# Pag4_Processador.net
KiCad netlist of a schematic drawn in Altium Designer
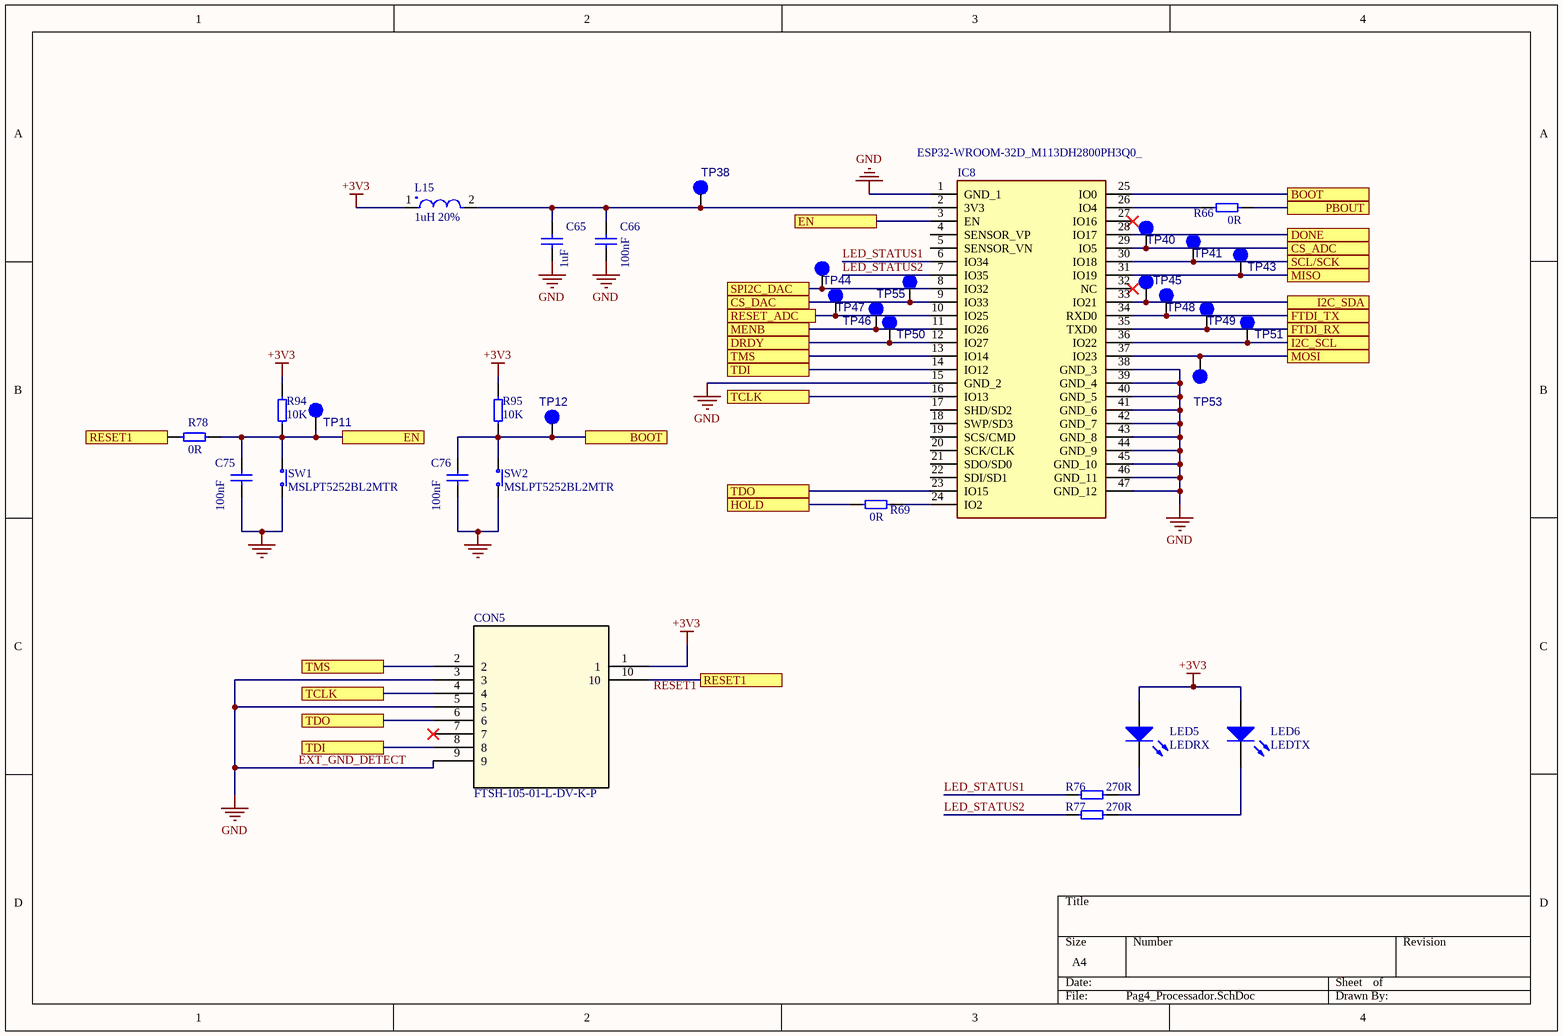
[diagram p0: Pag4_Processador.SchDoc]

(export (version "E")
  (design (tool "Eeschema 10.0.6"))
  (components
    (comp (ref "C65")
      (value "1uF")
      (footprint "0603")
      (description "Multilayer Ceramic Capacitors MLCC - SMD/SMT 1uF 25V 0603 10%")
      (fields
        (field (name "MANUFACTURER") "Samsung Electro-Mechanics")
        (field (name "MPN") "CL10A105KA8NNNC")
      )
      (libsource (lib "potenciostato") (part "CAP_1uF"))
    )
    (comp (ref "C66")
      (value "100nF")
      (footprint "0603")
      (description "Multilayer Ceramic Capacitors MLCC - SMD/SMT 100nF 16V 0603 10%")
      (fields (field (name "MPN") "C0603C104K4RACTU") (field (name "MANUFACTURER") "Kemet"))
      (libsource (lib "potenciostato") (part "Cap_1"))
    )
    (comp (ref "C75")
      (value "100nF")
      (footprint "0603")
      (description "Multilayer Ceramic Capacitors MLCC - SMD/SMT 100nF 16V 0603 10%")
      (fields (field (name "MPN") "C0603C104K4RACTU") (field (name "MANUFACTURER") "Kemet"))
      (libsource (lib "potenciostato") (part "Cap_1"))
    )
    (comp (ref "C76")
      (value "100nF")
      (footprint "0603")
      (description "Multilayer Ceramic Capacitors MLCC - SMD/SMT 100nF 16V 0603 10%")
      (fields (field (name "MPN") "C0603C104K4RACTU") (field (name "MANUFACTURER") "Kemet"))
      (libsource (lib "potenciostato") (part "Cap_1"))
    )
    (comp (ref "CON5")
      (value "FTSH-105-01-L-DV-K-P")
      (footprint "SAMTEC_FTSH-105-XX-X-DV")
      (description "No Description Available")
      (fields (field (name "MANUFACTURER") "Samtec") (field (name "MPN") "FTSH-105-01-L-DV-K-P-TR"))
      (libsource (lib "FTSH-105-01-L-DV-K-P") (part "FTSH-105-01-L-DV-K-P"))
    )
    (comp (ref "IC8")
      (value "ESP32-WROOM-32D_M113DH2800PH3Q0_")
      (footprint "SamacSys:ESP32WROOM32DM113DH2800PH3Q0")
      (description "Integrated Circuit")
      (fields
        (field (name "MANUFACTURER") "Espressif Systems")
        (field (name "MPN") "ESP32-WROOM-32D(M113DH2800PH3Q0)")
      )
      (libsource (lib "*") (part "ESP32-WROOM-32D_M113DH2800PH3Q0_"))
    )
    (comp (ref "L15")
      (value "1uH 20%")
      (footprint "SRP4020-1R5M")
      (description "Power Inductors - SMD 1uH 20% SMD 4012 AEC-Q200")
      (fields (field (name "MANUFACTURER") "Bourns") (field (name "MPN") "SRP4012TA-1R0M"))
      (libsource (lib "potenciostato") (part "IC_1uH"))
    )
    (comp (ref "LED5")
      (value "LEDRX")
      (footprint "0603 - LED")
      (description "Standard LEDs - SMD 0603 SMT CHIP LED 572nm")
      (fields (field (name "MANUFACTURER") "ROHM Semiconductor") (field (name "MPN") "SML-D13M8WT86"))
      (libsource (lib "LIBSCH_PULLUP") (part "LED"))
    )
    (comp (ref "LED6")
      (value "LEDTX")
      (footprint "0603 - LED")
      (description "Standard LEDs - SMD 0603 SMT CHIP LED 572nm")
      (fields (field (name "MANUFACTURER") "ROHM Semiconductor") (field (name "MPN") "SML-D13M8WT86"))
      (libsource (lib "LIBSCH_PULLUP") (part "LED"))
    )
    (comp (ref "R66")
      (value "0R")
      (footprint "0603")
      (description "Thick Film Resistors - SMD 0 Ohms 100 mW 0603 5%")
      (fields (field (name "MPN") "RC0603JR-070RL") (field (name "MANUFACTURER") "Yageo"))
      (libsource (lib "potenciostato") (part "Pullup_Res_0_0603_RES"))
    )
    (comp (ref "R69")
      (value "0R")
      (footprint "0603")
      (description "Thick Film Resistors - SMD 0 Ohms 100 mW 0603 5%")
      (fields (field (name "MPN") "RC0603JR-070RL") (field (name "MANUFACTURER") "Yageo"))
      (libsource (lib "potenciostato") (part "Pullup_Res_0_0603_RES"))
    )
    (comp (ref "R76")
      (value "270R")
      (footprint "0603_2")
      (description "Thick Film Resistors - SMD 270 Ohms 0603 100mW 1%")
      (fields (field (name "MANUFACTURER") "Yageo") (field (name "MPN") "RC0603FR-07270RL"))
      (libsource (lib "LIBSCH_PULLUP") (part "Res"))
    )
    (comp (ref "R77")
      (value "270R")
      (footprint "0603_2")
      (description "Thick Film Resistors - SMD 270 Ohms 0603 100mW 1%")
      (fields (field (name "MANUFACTURER") "Yageo") (field (name "MPN") "RC0603FR-07270RL"))
      (libsource (lib "LIBSCH_PULLUP") (part "Res"))
    )
    (comp (ref "R78")
      (value "0R")
      (footprint "0603")
      (description "Thick Film Resistors - SMD 0 Ohms 100 mW 0603 5%")
      (fields (field (name "MPN") "RC0603JR-070RL") (field (name "MANUFACTURER") "Yageo"))
      (libsource (lib "potenciostato") (part "Pullup_Res_0_0603_RES"))
    )
    (comp (ref "R94")
      (value "10K")
      (footprint "0603")
      (description "Thick Film Resistors - SMD 10 kOhms 100-200 mW 0603 1%")
      (fields (field (name "MPN") "RC0603FR-1310KL") (field (name "MANUFACTURER") "Yageo"))
      (libsource (lib "potenciostato") (part "Pullup_Res_100K_0603_RES"))
    )
    (comp (ref "R95")
      (value "10K")
      (footprint "0603")
      (description "Thick Film Resistors - SMD 10 kOhms 100-200 mW 0603 1%")
      (fields (field (name "MPN") "RC0603FR-1310KL") (field (name "MANUFACTURER") "Yageo"))
      (libsource (lib "potenciostato") (part "Pullup_Res_100K_0603_RES"))
    )
    (comp (ref "SW1")
      (value "MSLPT5252BL2MTR")
      (footprint "MSLPT5252BG1MTR_pullup")
      (description "Tactile Switch, SPNO, SMD, 160gf, 6.2x6.3x2.5mm")
      (fields (field (name "MANUFACTURER") "TE Connectivity / Alcoswitch"))
      (libsource (lib "Nordic Discrete DB") (part "SW-PB"))
    )
    (comp (ref "SW2")
      (value "MSLPT5252BL2MTR")
      (footprint "MSLPT5252BG1MTR_pullup")
      (description "Tactile Switch, SPNO, SMD, 160gf, 6.2x6.3x2.5mm")
      (fields (field (name "MANUFACTURER") "TE Connectivity / Alcoswitch"))
      (libsource (lib "Nordic Discrete DB") (part "SW-PB"))
    )
    (comp (ref "TP11")
      (value "Test Point")
      (footprint "TEST")
      (fields (field (name "MPN") "Test_Point") (field (name "MANUFACTURER") "DNA"))
      (libsource (lib "potenciostato") (part "TESTPOINT"))
    )
    (comp (ref "TP12")
      (value "Test Point")
      (footprint "TEST")
      (fields (field (name "MPN") "Test_Point") (field (name "MANUFACTURER") "DNA"))
      (libsource (lib "potenciostato") (part "TESTPOINT"))
    )
    (comp (ref "TP38")
      (value "Test Point")
      (footprint "TEST")
      (fields (field (name "MPN") "Test_Point") (field (name "MANUFACTURER") "DNA"))
      (libsource (lib "potenciostato") (part "TESTPOINT"))
    )
    (comp (ref "TP40")
      (value "Test Point")
      (footprint "TEST")
      (fields (field (name "MPN") "Test_Point") (field (name "MANUFACTURER") "DNA"))
      (libsource (lib "potenciostato") (part "TESTPOINT"))
    )
    (comp (ref "TP41")
      (value "Test Point")
      (footprint "TEST")
      (fields (field (name "MPN") "Test_Point") (field (name "MANUFACTURER") "DNA"))
      (libsource (lib "potenciostato") (part "TESTPOINT"))
    )
    (comp (ref "TP43")
      (value "Test Point")
      (footprint "TEST")
      (fields (field (name "MPN") "Test_Point") (field (name "MANUFACTURER") "DNA"))
      (libsource (lib "potenciostato") (part "TESTPOINT"))
    )
    (comp (ref "TP44")
      (value "Test Point")
      (footprint "TEST")
      (fields (field (name "MPN") "Test_Point") (field (name "MANUFACTURER") "DNA"))
      (libsource (lib "potenciostato") (part "TESTPOINT"))
    )
    (comp (ref "TP45")
      (value "Test Point")
      (footprint "TEST")
      (fields (field (name "MPN") "Test_Point") (field (name "MANUFACTURER") "DNA"))
      (libsource (lib "potenciostato") (part "TESTPOINT"))
    )
    (comp (ref "TP46")
      (value "Test Point")
      (footprint "TEST")
      (fields (field (name "MPN") "Test_Point") (field (name "MANUFACTURER") "DNA"))
      (libsource (lib "potenciostato") (part "TESTPOINT"))
    )
    (comp (ref "TP47")
      (value "Test Point")
      (footprint "TEST")
      (fields (field (name "MPN") "Test_Point") (field (name "MANUFACTURER") "DNA"))
      (libsource (lib "potenciostato") (part "TESTPOINT"))
    )
    (comp (ref "TP48")
      (value "Test Point")
      (footprint "TEST")
      (fields (field (name "MPN") "Test_Point") (field (name "MANUFACTURER") "DNA"))
      (libsource (lib "potenciostato") (part "TESTPOINT"))
    )
    (comp (ref "TP49")
      (value "Test Point")
      (footprint "TEST")
      (fields (field (name "MPN") "Test_Point") (field (name "MANUFACTURER") "DNA"))
      (libsource (lib "potenciostato") (part "TESTPOINT"))
    )
    (comp (ref "TP50")
      (value "Test Point")
      (footprint "TEST")
      (fields (field (name "MPN") "Test_Point") (field (name "MANUFACTURER") "DNA"))
      (libsource (lib "potenciostato") (part "TESTPOINT"))
    )
    (comp (ref "TP51")
      (value "Test Point")
      (footprint "TEST")
      (fields (field (name "MPN") "Test_Point") (field (name "MANUFACTURER") "DNA"))
      (libsource (lib "potenciostato") (part "TESTPOINT"))
    )
    (comp (ref "TP53")
      (value "Test Point")
      (footprint "TEST")
      (fields (field (name "MPN") "Test_Point") (field (name "MANUFACTURER") "DNA"))
      (libsource (lib "potenciostato") (part "TESTPOINT"))
    )
    (comp (ref "TP55")
      (value "Test Point")
      (footprint "TEST")
      (fields (field (name "MPN") "Test_Point") (field (name "MANUFACTURER") "DNA"))
      (libsource (lib "potenciostato") (part "TESTPOINT"))
    )
  )
  (nets
    (net (code "1") (name "+3V3") (class "Default")
      (node (ref "CON5") (pin "1") (pinfunction "1_1") (pintype "passive"))
      (node (ref "L15") (pin "1") (pinfunction "1_1") (pintype "passive"))
      (node (ref "LED5") (pin "1") (pinfunction "A_1") (pintype "passive"))
      (node (ref "LED6") (pin "1") (pinfunction "A_1") (pintype "passive"))
      (node (ref "R94") (pin "2") (pinfunction "2_2") (pintype "passive"))
      (node (ref "R95") (pin "2") (pinfunction "2_2") (pintype "passive"))
    )
    (net (code "2") (name "/BOOT") (class "Default")
      (node (ref "C76") (pin "2") (pinfunction "2_2") (pintype "passive"))
      (node (ref "IC8") (pin "25") (pinfunction "IO0_25") (pintype "passive"))
      (node (ref "R95") (pin "1") (pinfunction "1_1") (pintype "passive"))
      (node (ref "SW2") (pin "2") (pinfunction "COM_2") (pintype "passive"))
      (node (ref "TP12") (pin "1") (pinfunction "TP_1") (pintype "passive"))
    )
    (net (code "3") (name "/CS_ADC") (class "Default")
      (node (ref "IC8") (pin "29") (pinfunction "IO5_29") (pintype "passive"))
      (node (ref "TP40") (pin "1") (pinfunction "TP_1") (pintype "passive"))
    )
    (net (code "4") (name "/CS_DAC") (class "Default")
      (node (ref "IC8") (pin "9") (pinfunction "IO33_9") (pintype "passive"))
      (node (ref "TP55") (pin "1") (pinfunction "TP_1") (pintype "passive"))
    )
    (net (code "5") (name "/DONE") (class "Default")
      (node (ref "IC8") (pin "28") (pinfunction "IO17_28") (pintype "passive"))
    )
    (net (code "6") (name "/DRDY") (class "Default")
      (node (ref "IC8") (pin "12") (pinfunction "IO27_12") (pintype "passive"))
      (node (ref "TP50") (pin "1") (pinfunction "TP_1") (pintype "passive"))
    )
    (net (code "7") (name "/EN") (class "Default")
      (node (ref "C75") (pin "2") (pinfunction "2_2") (pintype "passive"))
      (node (ref "IC8") (pin "3") (pinfunction "EN_3") (pintype "passive"))
      (node (ref "R78") (pin "1") (pinfunction "1_1") (pintype "passive"))
      (node (ref "R94") (pin "1") (pinfunction "1_1") (pintype "passive"))
      (node (ref "SW1") (pin "2") (pinfunction "COM_2") (pintype "passive"))
      (node (ref "TP11") (pin "1") (pinfunction "TP_1") (pintype "passive"))
    )
    (net (code "8") (name "/FTDI_RX") (class "Default")
      (node (ref "IC8") (pin "35") (pinfunction "TXD0_35") (pintype "passive"))
      (node (ref "TP49") (pin "1") (pinfunction "TP_1") (pintype "passive"))
    )
    (net (code "9") (name "/FTDI_TX") (class "Default")
      (node (ref "IC8") (pin "34") (pinfunction "RXD0_34") (pintype "passive"))
      (node (ref "TP48") (pin "1") (pinfunction "TP_1") (pintype "passive"))
    )
    (net (code "10") (name "/HOLD") (class "Default")
      (node (ref "R69") (pin "2") (pinfunction "2_2") (pintype "passive"))
    )
    (net (code "11") (name "/I2C_SCL") (class "Default")
      (node (ref "IC8") (pin "36") (pinfunction "IO22_36") (pintype "passive"))
      (node (ref "TP51") (pin "1") (pinfunction "TP_1") (pintype "passive"))
    )
    (net (code "12") (name "/I2C_SDA") (class "Default")
      (node (ref "IC8") (pin "33") (pinfunction "IO21_33") (pintype "passive"))
      (node (ref "TP45") (pin "1") (pinfunction "TP_1") (pintype "passive"))
    )
    (net (code "13") (name "/LED_STATUS1") (class "Default")
      (node (ref "IC8") (pin "6") (pinfunction "IO34_6") (pintype "passive"))
      (node (ref "R76") (pin "1") (pinfunction "1_1") (pintype "passive"))
    )
    (net (code "14") (name "/LED_STATUS2") (class "Default")
      (node (ref "IC8") (pin "7") (pinfunction "IO35_7") (pintype "passive"))
      (node (ref "R77") (pin "1") (pinfunction "1_1") (pintype "passive"))
    )
    (net (code "15") (name "/MENB") (class "Default")
      (node (ref "IC8") (pin "11") (pinfunction "IO26_11") (pintype "passive"))
      (node (ref "TP46") (pin "1") (pinfunction "TP_1") (pintype "passive"))
    )
    (net (code "16") (name "/MISO") (class "Default")
      (node (ref "IC8") (pin "31") (pinfunction "IO19_31") (pintype "passive"))
      (node (ref "TP43") (pin "1") (pinfunction "TP_1") (pintype "passive"))
    )
    (net (code "17") (name "/MOSI") (class "Default")
      (node (ref "IC8") (pin "37") (pinfunction "IO23_37") (pintype "passive"))
      (node (ref "TP53") (pin "1") (pinfunction "TP_1") (pintype "passive"))
    )
    (net (code "18") (name "/PBOUT") (class "Default")
      (node (ref "R66") (pin "1") (pinfunction "1_1") (pintype "passive"))
    )
    (net (code "19") (name "/RESET1") (class "Default")
      (node (ref "CON5") (pin "10") (pinfunction "10_10") (pintype "passive"))
      (node (ref "R78") (pin "2") (pinfunction "2_2") (pintype "passive"))
    )
    (net (code "20") (name "/RESET_ADC") (class "Default")
      (node (ref "IC8") (pin "10") (pinfunction "IO25_10") (pintype "passive"))
      (node (ref "TP47") (pin "1") (pinfunction "TP_1") (pintype "passive"))
    )
    (net (code "21") (name "/SCL{slash}SCK") (class "Default")
      (node (ref "IC8") (pin "30") (pinfunction "IO18_30") (pintype "passive"))
      (node (ref "TP41") (pin "1") (pinfunction "TP_1") (pintype "passive"))
    )
    (net (code "22") (name "/SPI2C_DAC") (class "Default")
      (node (ref "IC8") (pin "8") (pinfunction "IO32_8") (pintype "passive"))
      (node (ref "TP44") (pin "1") (pinfunction "TP_1") (pintype "passive"))
    )
    (net (code "23") (name "/TCLK") (class "Default")
      (node (ref "CON5") (pin "4") (pinfunction "4_4") (pintype "passive"))
      (node (ref "IC8") (pin "16") (pinfunction "IO13_16") (pintype "passive"))
    )
    (net (code "24") (name "/TDI") (class "Default")
      (node (ref "CON5") (pin "8") (pinfunction "8_8") (pintype "passive"))
      (node (ref "IC8") (pin "14") (pinfunction "IO12_14") (pintype "passive"))
    )
    (net (code "25") (name "/TDO") (class "Default")
      (node (ref "CON5") (pin "6") (pinfunction "6_6") (pintype "passive"))
      (node (ref "IC8") (pin "23") (pinfunction "IO15_23") (pintype "passive"))
    )
    (net (code "26") (name "/TMS") (class "Default")
      (node (ref "CON5") (pin "2") (pinfunction "2_2") (pintype "passive"))
      (node (ref "IC8") (pin "13") (pinfunction "IO14_13") (pintype "passive"))
    )
    (net (code "27") (name "GND") (class "Default")
      (node (ref "C65") (pin "1") (pinfunction "1_1") (pintype "passive"))
      (node (ref "C66") (pin "1") (pinfunction "1_1") (pintype "passive"))
      (node (ref "C75") (pin "1") (pinfunction "1_1") (pintype "passive"))
      (node (ref "C76") (pin "1") (pinfunction "1_1") (pintype "passive"))
      (node (ref "CON5") (pin "3") (pinfunction "3_3") (pintype "passive"))
      (node (ref "CON5") (pin "5") (pinfunction "5_5") (pintype "passive"))
      (node (ref "CON5") (pin "9") (pinfunction "9_9") (pintype "passive"))
      (node (ref "IC8") (pin "1") (pinfunction "GND_1_1") (pintype "passive"))
      (node (ref "IC8") (pin "15") (pinfunction "GND_2_15") (pintype "passive"))
      (node (ref "IC8") (pin "38") (pinfunction "GND_3_38") (pintype "passive"))
      (node (ref "IC8") (pin "39") (pinfunction "GND_4_39") (pintype "passive"))
      (node (ref "IC8") (pin "40") (pinfunction "GND_5_40") (pintype "passive"))
      (node (ref "IC8") (pin "41") (pinfunction "GND_6_41") (pintype "passive"))
      (node (ref "IC8") (pin "42") (pinfunction "GND_7_42") (pintype "passive"))
      (node (ref "IC8") (pin "43") (pinfunction "GND_8_43") (pintype "passive"))
      (node (ref "IC8") (pin "44") (pinfunction "GND_9_44") (pintype "passive"))
      (node (ref "IC8") (pin "45") (pinfunction "GND_10_45") (pintype "passive"))
      (node (ref "IC8") (pin "46") (pinfunction "GND_11_46") (pintype "passive"))
      (node (ref "IC8") (pin "47") (pinfunction "GND_12_47") (pintype "passive"))
      (node (ref "SW1") (pin "1") (pinfunction "N.O_1") (pintype "passive"))
      (node (ref "SW2") (pin "1") (pinfunction "N.O_1") (pintype "passive"))
    )
    (net (code "28") (name "Net-(IC8-3V3)") (class "Default")
      (node (ref "C65") (pin "2") (pinfunction "2_2") (pintype "passive"))
      (node (ref "C66") (pin "2") (pinfunction "2_2") (pintype "passive"))
      (node (ref "IC8") (pin "2") (pinfunction "3V3_2") (pintype "passive"))
      (node (ref "L15") (pin "2") (pinfunction "2_2") (pintype "passive"))
      (node (ref "TP38") (pin "1") (pinfunction "TP_1") (pintype "passive"))
    )
    (net (code "29") (name "Net-(IC8-IO2)") (class "Default")
      (node (ref "IC8") (pin "24") (pinfunction "IO2_24") (pintype "passive"))
      (node (ref "R69") (pin "1") (pinfunction "1_1") (pintype "passive"))
    )
    (net (code "30") (name "Net-(IC8-IO4)") (class "Default")
      (node (ref "IC8") (pin "26") (pinfunction "IO4_26") (pintype "passive"))
      (node (ref "R66") (pin "2") (pinfunction "2_2") (pintype "passive"))
    )
    (net (code "31") (name "Net-(LED5-K)") (class "Default")
      (node (ref "LED5") (pin "2") (pinfunction "K_2") (pintype "passive"))
      (node (ref "R76") (pin "2") (pinfunction "2_2") (pintype "passive"))
    )
    (net (code "32") (name "Net-(LED6-K)") (class "Default")
      (node (ref "LED6") (pin "2") (pinfunction "K_2") (pintype "passive"))
      (node (ref "R77") (pin "2") (pinfunction "2_2") (pintype "passive"))
    )
    (net (code "33") (name "unconnected-(CON5-Pad7)") (class "Default")
      (node (ref "CON5") (pin "7") (pinfunction "7_7") (pintype "passive+no_connect"))
    )
    (net (code "34") (name "unconnected-(IC8-IO16-Pad27)") (class "Default")
      (node (ref "IC8") (pin "27") (pinfunction "IO16_27") (pintype "passive+no_connect"))
    )
    (net (code "35") (name "unconnected-(IC8-NC-Pad32)") (class "Default")
      (node (ref "IC8") (pin "32") (pinfunction "NC_32") (pintype "passive+no_connect"))
    )
    (net (code "36") (name "unconnected-(IC8-SCK{slash}CLK-Pad20)") (class "Default")
      (node (ref "IC8") (pin "20") (pinfunction "SCK/CLK_20") (pintype "passive"))
    )
    (net (code "37") (name "unconnected-(IC8-SCS{slash}CMD-Pad19)") (class "Default")
      (node (ref "IC8") (pin "19") (pinfunction "SCS/CMD_19") (pintype "passive"))
    )
    (net (code "38") (name "unconnected-(IC8-SDI{slash}SD1-Pad22)") (class "Default")
      (node (ref "IC8") (pin "22") (pinfunction "SDI/SD1_22") (pintype "passive"))
    )
    (net (code "39") (name "unconnected-(IC8-SDO{slash}SD0-Pad21)") (class "Default")
      (node (ref "IC8") (pin "21") (pinfunction "SDO/SD0_21") (pintype "passive"))
    )
    (net (code "40") (name "unconnected-(IC8-SENSOR_VN-Pad5)") (class "Default")
      (node (ref "IC8") (pin "5") (pinfunction "SENSOR_VN_5") (pintype "passive"))
    )
    (net (code "41") (name "unconnected-(IC8-SENSOR_VP-Pad4)") (class "Default")
      (node (ref "IC8") (pin "4") (pinfunction "SENSOR_VP_4") (pintype "passive"))
    )
    (net (code "42") (name "unconnected-(IC8-SHD{slash}SD2-Pad17)") (class "Default")
      (node (ref "IC8") (pin "17") (pinfunction "SHD/SD2_17") (pintype "passive"))
    )
    (net (code "43") (name "unconnected-(IC8-SWP{slash}SD3-Pad18)") (class "Default")
      (node (ref "IC8") (pin "18") (pinfunction "SWP/SD3_18") (pintype "passive"))
    )
  )
)
